# a1200_keyboard_adapter.net
KiCad netlist of a schematic drawn in Altium Designer
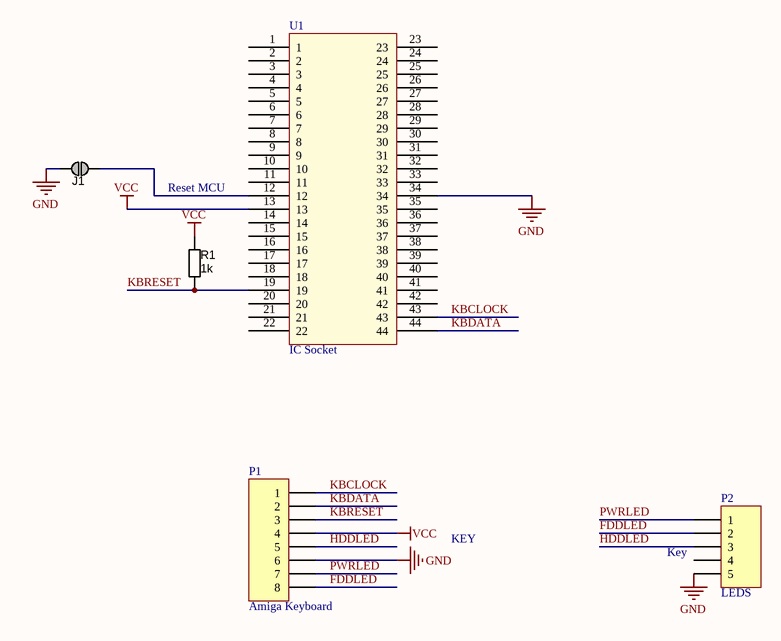
[diagram p0: a1200_keyboard_adapter.SchDoc]

(export (version "E")
  (design (tool "Eeschema 10.0.6"))
  (components
    (comp (ref "J1")
      (value "Jumper")
      (footprint "JUMP1")
      (description "SMD jumper")
      (libsource (lib "PBL - Pads and Jumpers") (part "JUMP1"))
    )
    (comp (ref "P1")
      (value "Amiga Keyboard")
      (footprint "HDR1X8")
      (description "Header, 8-Pin")
      (fields (field (name "PUBLISHER") "Altium Limited"))
      (libsource (lib "Miscellaneous Connectors") (part "Header 8"))
    )
    (comp (ref "P2")
      (value "LEDS")
      (footprint "HDR1X5")
      (description "Header, 5-Pin")
      (fields (field (name "PUBLISHER") "Altium Limited"))
      (libsource (lib "Miscellaneous Connectors") (part "Header 5"))
    )
    (comp (ref "R1")
      (value "1k")
      (footprint "RESC2012N_ZERO")
      (description "Resistor SMD chip 0.0 Ohm 0.125W 0805")
      (fields (field (name "Comment") "0805"))
      (libsource (lib "PBL - Resistors") (part "RES_0R_0805"))
    )
    (comp (ref "U1")
      (value "IC Socket")
      (footprint "PLCC44_THD")
      (description "44-pin IC socket")
      (libsource (lib "small-PCBs") (part "IC_SOCKET_44"))
    )
  )
  (nets
    (net (code "1") (name "/FDDLED") (class "Default")
      (node (ref "P1") (pin "8") (pinfunction "8_8") (pintype "passive"))
      (node (ref "P2") (pin "2") (pinfunction "2_2") (pintype "passive"))
    )
    (net (code "2") (name "/HDDLED") (class "Default")
      (node (ref "P1") (pin "5") (pinfunction "5_5") (pintype "passive"))
      (node (ref "P2") (pin "3") (pinfunction "3_3") (pintype "passive"))
    )
    (net (code "3") (name "/KBCLOCK") (class "Default")
      (node (ref "P1") (pin "1") (pinfunction "1_1") (pintype "passive"))
      (node (ref "U1") (pin "43") (pinfunction "43_43") (pintype "passive"))
    )
    (net (code "4") (name "/KBDATA") (class "Default")
      (node (ref "P1") (pin "2") (pinfunction "2_2") (pintype "passive"))
      (node (ref "U1") (pin "44") (pinfunction "44_44") (pintype "passive"))
    )
    (net (code "5") (name "/KBRESET") (class "Default")
      (node (ref "P1") (pin "3") (pinfunction "3_3") (pintype "passive"))
      (node (ref "R1") (pin "1") (pinfunction "1_1") (pintype "passive"))
      (node (ref "U1") (pin "19") (pinfunction "19_19") (pintype "passive"))
    )
    (net (code "6") (name "/PWRLED") (class "Default")
      (node (ref "P1") (pin "7") (pinfunction "7_7") (pintype "passive"))
      (node (ref "P2") (pin "1") (pinfunction "1_1") (pintype "passive"))
    )
    (net (code "7") (name "GND") (class "Default")
      (node (ref "J1") (pin "2") (pintype "passive"))
      (node (ref "P1") (pin "6") (pinfunction "6_6") (pintype "passive"))
      (node (ref "P2") (pin "5") (pinfunction "5_5") (pintype "passive"))
      (node (ref "U1") (pin "34") (pinfunction "34_34") (pintype "passive"))
    )
    (net (code "8") (name "Net-(J1-Pad1)") (class "Default")
      (node (ref "J1") (pin "1") (pintype "passive"))
      (node (ref "U1") (pin "12") (pinfunction "12_12") (pintype "passive"))
    )
    (net (code "9") (name "VCC") (class "Default")
      (node (ref "P1") (pin "4") (pinfunction "4_4") (pintype "passive"))
      (node (ref "R1") (pin "2") (pinfunction "2_2") (pintype "passive"))
      (node (ref "U1") (pin "13") (pinfunction "13_13") (pintype "passive"))
    )
    (net (code "10") (name "unconnected-(P2-Pad4)") (class "Default")
      (node (ref "P2") (pin "4") (pinfunction "4_4") (pintype "passive"))
    )
    (net (code "11") (name "unconnected-(U1-Pad1)") (class "Default")
      (node (ref "U1") (pin "1") (pinfunction "1_1") (pintype "passive"))
    )
    (net (code "12") (name "unconnected-(U1-Pad2)") (class "Default")
      (node (ref "U1") (pin "2") (pinfunction "2_2") (pintype "passive"))
    )
    (net (code "13") (name "unconnected-(U1-Pad3)") (class "Default")
      (node (ref "U1") (pin "3") (pinfunction "3_3") (pintype "passive"))
    )
    (net (code "14") (name "unconnected-(U1-Pad4)") (class "Default")
      (node (ref "U1") (pin "4") (pinfunction "4_4") (pintype "passive"))
    )
    (net (code "15") (name "unconnected-(U1-Pad5)") (class "Default")
      (node (ref "U1") (pin "5") (pinfunction "5_5") (pintype "passive"))
    )
    (net (code "16") (name "unconnected-(U1-Pad6)") (class "Default")
      (node (ref "U1") (pin "6") (pinfunction "6_6") (pintype "passive"))
    )
    (net (code "17") (name "unconnected-(U1-Pad7)") (class "Default")
      (node (ref "U1") (pin "7") (pinfunction "7_7") (pintype "passive"))
    )
    (net (code "18") (name "unconnected-(U1-Pad8)") (class "Default")
      (node (ref "U1") (pin "8") (pinfunction "8_8") (pintype "passive"))
    )
    (net (code "19") (name "unconnected-(U1-Pad9)") (class "Default")
      (node (ref "U1") (pin "9") (pinfunction "9_9") (pintype "passive"))
    )
    (net (code "20") (name "unconnected-(U1-Pad10)") (class "Default")
      (node (ref "U1") (pin "10") (pinfunction "10_10") (pintype "passive"))
    )
    (net (code "21") (name "unconnected-(U1-Pad11)") (class "Default")
      (node (ref "U1") (pin "11") (pinfunction "11_11") (pintype "passive"))
    )
    (net (code "22") (name "unconnected-(U1-Pad14)") (class "Default")
      (node (ref "U1") (pin "14") (pinfunction "14_14") (pintype "passive"))
    )
    (net (code "23") (name "unconnected-(U1-Pad15)") (class "Default")
      (node (ref "U1") (pin "15") (pinfunction "15_15") (pintype "passive"))
    )
    (net (code "24") (name "unconnected-(U1-Pad16)") (class "Default")
      (node (ref "U1") (pin "16") (pinfunction "16_16") (pintype "passive"))
    )
    (net (code "25") (name "unconnected-(U1-Pad17)") (class "Default")
      (node (ref "U1") (pin "17") (pinfunction "17_17") (pintype "passive"))
    )
    (net (code "26") (name "unconnected-(U1-Pad18)") (class "Default")
      (node (ref "U1") (pin "18") (pinfunction "18_18") (pintype "passive"))
    )
    (net (code "27") (name "unconnected-(U1-Pad20)") (class "Default")
      (node (ref "U1") (pin "20") (pinfunction "20_20") (pintype "passive"))
    )
    (net (code "28") (name "unconnected-(U1-Pad21)") (class "Default")
      (node (ref "U1") (pin "21") (pinfunction "21_21") (pintype "passive"))
    )
    (net (code "29") (name "unconnected-(U1-Pad22)") (class "Default")
      (node (ref "U1") (pin "22") (pinfunction "22_22") (pintype "passive"))
    )
    (net (code "30") (name "unconnected-(U1-Pad23)") (class "Default")
      (node (ref "U1") (pin "23") (pinfunction "23_23") (pintype "passive"))
    )
    (net (code "31") (name "unconnected-(U1-Pad24)") (class "Default")
      (node (ref "U1") (pin "24") (pinfunction "24_24") (pintype "passive"))
    )
    (net (code "32") (name "unconnected-(U1-Pad25)") (class "Default")
      (node (ref "U1") (pin "25") (pinfunction "25_25") (pintype "passive"))
    )
    (net (code "33") (name "unconnected-(U1-Pad26)") (class "Default")
      (node (ref "U1") (pin "26") (pinfunction "26_26") (pintype "passive"))
    )
    (net (code "34") (name "unconnected-(U1-Pad27)") (class "Default")
      (node (ref "U1") (pin "27") (pinfunction "27_27") (pintype "passive"))
    )
    (net (code "35") (name "unconnected-(U1-Pad28)") (class "Default")
      (node (ref "U1") (pin "28") (pinfunction "28_28") (pintype "passive"))
    )
    (net (code "36") (name "unconnected-(U1-Pad29)") (class "Default")
      (node (ref "U1") (pin "29") (pinfunction "29_29") (pintype "passive"))
    )
    (net (code "37") (name "unconnected-(U1-Pad30)") (class "Default")
      (node (ref "U1") (pin "30") (pinfunction "30_30") (pintype "passive"))
    )
    (net (code "38") (name "unconnected-(U1-Pad31)") (class "Default")
      (node (ref "U1") (pin "31") (pinfunction "31_31") (pintype "passive"))
    )
    (net (code "39") (name "unconnected-(U1-Pad32)") (class "Default")
      (node (ref "U1") (pin "32") (pinfunction "32_32") (pintype "passive"))
    )
    (net (code "40") (name "unconnected-(U1-Pad33)") (class "Default")
      (node (ref "U1") (pin "33") (pinfunction "33_33") (pintype "passive"))
    )
    (net (code "41") (name "unconnected-(U1-Pad35)") (class "Default")
      (node (ref "U1") (pin "35") (pinfunction "35_35") (pintype "passive"))
    )
    (net (code "42") (name "unconnected-(U1-Pad36)") (class "Default")
      (node (ref "U1") (pin "36") (pinfunction "36_36") (pintype "passive"))
    )
    (net (code "43") (name "unconnected-(U1-Pad37)") (class "Default")
      (node (ref "U1") (pin "37") (pinfunction "37_37") (pintype "passive"))
    )
    (net (code "44") (name "unconnected-(U1-Pad38)") (class "Default")
      (node (ref "U1") (pin "38") (pinfunction "38_38") (pintype "passive"))
    )
    (net (code "45") (name "unconnected-(U1-Pad39)") (class "Default")
      (node (ref "U1") (pin "39") (pinfunction "39_39") (pintype "passive"))
    )
    (net (code "46") (name "unconnected-(U1-Pad40)") (class "Default")
      (node (ref "U1") (pin "40") (pinfunction "40_40") (pintype "passive"))
    )
    (net (code "47") (name "unconnected-(U1-Pad41)") (class "Default")
      (node (ref "U1") (pin "41") (pinfunction "41_41") (pintype "passive"))
    )
    (net (code "48") (name "unconnected-(U1-Pad42)") (class "Default")
      (node (ref "U1") (pin "42") (pinfunction "42_42") (pintype "passive"))
    )
  )
)
